# Sheet1.net
KiCad netlist of a schematic drawn in Altium Designer
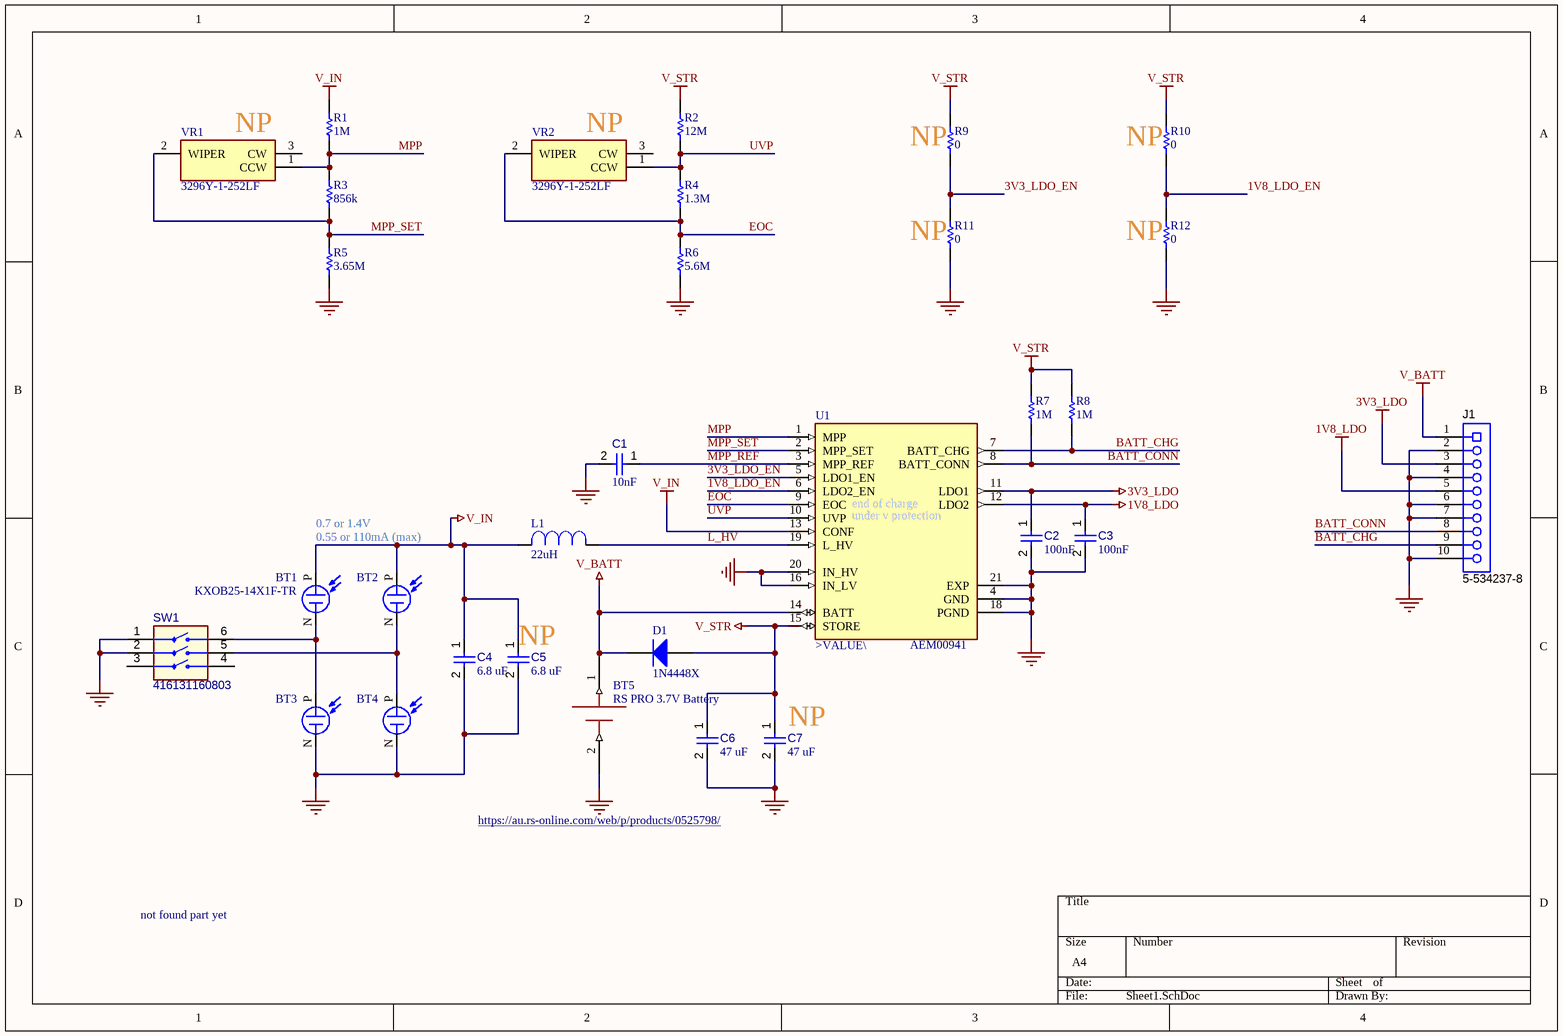
[diagram p0: Sheet1.SchDoc]

(export (version "E")
  (design (tool "Eeschema 10.0.6"))
  (components
    (comp (ref "BT1")
      (value "KXOB25-14X1F-TR")
      (footprint "SOLAR_KXOB25-14X1F-TR")
      (description "Monocrystalline Solar Cell 30.7 mW 690 mV")
      (fields (field (name "MF") "ANYSOLAR Ltd"))
      (libsource (lib "KXOB25-14X1F-TR") (part "KXOB25-14X1F-TR"))
    )
    (comp (ref "BT2")
      (value "KXOB25-14X1F-TR")
      (footprint "SOLAR_KXOB25-14X1F-TR")
      (description "Monocrystalline Solar Cell 30.7 mW 690 mV")
      (fields (field (name "MF") "ANYSOLAR Ltd"))
      (libsource (lib "KXOB25-14X1F-TR") (part "KXOB25-14X1F-TR"))
    )
    (comp (ref "BT3")
      (value "KXOB25-14X1F-TR")
      (footprint "SOLAR_KXOB25-14X1F-TR")
      (description "Monocrystalline Solar Cell 30.7 mW 690 mV")
      (fields (field (name "MF") "ANYSOLAR Ltd"))
      (libsource (lib "KXOB25-14X1F-TR") (part "KXOB25-14X1F-TR"))
    )
    (comp (ref "BT4")
      (value "KXOB25-14X1F-TR")
      (footprint "SOLAR_KXOB25-14X1F-TR")
      (description "Monocrystalline Solar Cell 30.7 mW 690 mV")
      (fields (field (name "MF") "ANYSOLAR Ltd"))
      (libsource (lib "KXOB25-14X1F-TR") (part "KXOB25-14X1F-TR"))
    )
    (comp (ref "BT5") (value "RS PRO 3.7V Battery") (libsource (lib "Schlib3") (part "RS PRO 3.7V Battery")))
    (comp (ref "C1")
      (value "10nF")
      (footprint "CAPC1608X94X35NL15T15")
      (description "Chip Capacitor, 1 uF, +/- 10%, 16 V, 0603 (1608 Metric)")
      (fields (field (name "TOLERANCE") "10%") (field (name "Comment") "Capacitor 1 uF +/- 10% 16 V 0603"))
      (libsource (lib "University of New South Wales") (part "CAP-NP-2"))
    )
    (comp (ref "C2")
      (value "100nF")
      (footprint "CAPC1608X94X35NL15T15")
      (description "Chip Capacitor, 1 uF, +/- 10%, 16 V, 0603 (1608 Metric)")
      (fields (field (name "TOLERANCE") "10%") (field (name "Comment") "Capacitor 1 uF +/- 10% 16 V 0603"))
      (libsource (lib "University of New South Wales") (part "CAP-NP-2"))
    )
    (comp (ref "C3")
      (value "100nF")
      (footprint "CAPC1608X94X35NL15T15")
      (description "Chip Capacitor, 1 uF, +/- 10%, 16 V, 0603 (1608 Metric)")
      (fields (field (name "TOLERANCE") "10%") (field (name "Comment") "Capacitor 1 uF +/- 10% 16 V 0603"))
      (libsource (lib "University of New South Wales") (part "CAP-NP-2"))
    )
    (comp (ref "C4")
      (value "6.8 uF")
      (footprint "CAPC0805(2012)145_L")
      (description "Chip Capacitor, 100µF +/-20%, 6.3V, 0805, Thickness 1.45 mm")
      (fields (field (name "TOLERANCE") "10%") (field (name "Comment") "Capacitor 100µF +/-20% 6.3V 0805"))
      (libsource (lib "University of New South Wales") (part "CAP-NP-2"))
    )
    (comp (ref "C5")
      (value "6.8 uF")
      (footprint "CAPC0805(2012)145_L")
      (description "Chip Capacitor, 100µF +/-20%, 6.3V, 0805, Thickness 1.45 mm")
      (fields (field (name "TOLERANCE") "10%") (field (name "Comment") "Capacitor 100µF +/-20% 6.3V 0805"))
      (libsource (lib "University of New South Wales") (part "CAP-NP-2"))
    )
    (comp (ref "C6")
      (value "47 uF")
      (footprint "CAPC0805(2012)145_L")
      (description "Chip Capacitor, 100µF +/-20%, 6.3V, 0805, Thickness 1.45 mm")
      (fields (field (name "TOLERANCE") "10%") (field (name "Comment") "Capacitor 100µF +/-20% 6.3V 0805"))
      (libsource (lib "University of New South Wales") (part "CAP-NP-2"))
    )
    (comp (ref "C7")
      (value "47 uF")
      (footprint "CAPC0805(2012)145_L")
      (description "Chip Capacitor, 100µF +/-20%, 6.3V, 0805, Thickness 1.45 mm")
      (fields (field (name "TOLERANCE") "10%") (field (name "Comment") "Capacitor 100µF +/-20% 6.3V 0805"))
      (libsource (lib "University of New South Wales") (part "CAP-NP-2"))
    )
    (comp (ref "D1")
      (value "1N4448X")
      (footprint "FAIR-SOD-323_V")
      (description "Small Signal Diode, 75 V, 0.15 A, -55 to 150 degC, 2-Pin SOD-323, RoHS, Tape and Reel")
      (fields (field (name "MANUFACTURER") "Fairchild"))
      (libsource (lib "University of New South Wales") (part "D-AK-2"))
    )
    (comp (ref "J1")
      (value "5-534237-8")
      (footprint "TECO-5-534237-8_V")
      (fields (field (name "MANUFACTURER") "TE Connectivity"))
      (libsource (lib "University of New South Wales") (part "CN-1P-F-R10"))
    )
    (comp (ref "L1")
      (value "22uH")
      (footprint "INDM125125X600N")
      (fields (field (name "MF") "Eaton") (field (name "MP") "DR125471R"))
      (libsource (lib "DR125-471-R") (part "DR125-471-R"))
    )
    (comp (ref "R1")
      (value "1M")
      (footprint "RESC1608X55X25ML10T15")
      (description "Chip Resistor, 0 Ohm, 0.1 W, -55 to 155 degC, 0603 (1608 Metric)")
      (fields (field (name "POWER") "100mW") (field (name "TOLERANCE") "5%"))
      (libsource (lib "University of New South Wales") (part "RES-2"))
    )
    (comp (ref "R2")
      (value "12M")
      (footprint "RESC1608X55X25ML10T15")
      (description "Chip Resistor, 0 Ohm, 0.1 W, -55 to 155 degC, 0603 (1608 Metric)")
      (fields (field (name "POWER") "100mW") (field (name "TOLERANCE") "5%"))
      (libsource (lib "University of New South Wales") (part "RES-2"))
    )
    (comp (ref "R3")
      (value "856k")
      (footprint "RESC1608X55X25ML10T15")
      (description "Chip Resistor, 0 Ohm, 0.1 W, -55 to 155 degC, 0603 (1608 Metric)")
      (fields (field (name "POWER") "100mW") (field (name "TOLERANCE") "5%"))
      (libsource (lib "University of New South Wales") (part "RES-2"))
    )
    (comp (ref "R4")
      (value "1.3M")
      (footprint "RESC1608X55X25ML10T15")
      (description "Chip Resistor, 0 Ohm, 0.1 W, -55 to 155 degC, 0603 (1608 Metric)")
      (fields (field (name "POWER") "100mW") (field (name "TOLERANCE") "5%"))
      (libsource (lib "University of New South Wales") (part "RES-2"))
    )
    (comp (ref "R5")
      (value "3.65M")
      (footprint "RESC1608X55X25ML10T15")
      (description "Chip Resistor, 0 Ohm, 0.1 W, -55 to 155 degC, 0603 (1608 Metric)")
      (fields (field (name "POWER") "100mW") (field (name "TOLERANCE") "5%"))
      (libsource (lib "University of New South Wales") (part "RES-2"))
    )
    (comp (ref "R6")
      (value "5.6M")
      (footprint "RESC1608X55X25ML10T15")
      (description "Chip Resistor, 0 Ohm, 0.1 W, -55 to 155 degC, 0603 (1608 Metric)")
      (fields (field (name "POWER") "100mW") (field (name "TOLERANCE") "5%"))
      (libsource (lib "University of New South Wales") (part "RES-2"))
    )
    (comp (ref "R7")
      (value "1M")
      (footprint "RESC1608X55X25ML10T15")
      (description "Chip Resistor, 0 Ohm, 0.1 W, -55 to 155 degC, 0603 (1608 Metric)")
      (fields (field (name "POWER") "100mW") (field (name "TOLERANCE") "5%"))
      (libsource (lib "University of New South Wales") (part "RES-2"))
    )
    (comp (ref "R8")
      (value "1M")
      (footprint "RESC1608X55X25ML10T15")
      (description "Chip Resistor, 0 Ohm, 0.1 W, -55 to 155 degC, 0603 (1608 Metric)")
      (fields (field (name "POWER") "100mW") (field (name "TOLERANCE") "5%"))
      (libsource (lib "University of New South Wales") (part "RES-2"))
    )
    (comp (ref "R9")
      (value "0")
      (footprint "RESC1005X40X25ML05T10")
      (description "Chip Resistor, 0 Ohm, 0.063 W, -55 to 155 degC, 0402 (1005 Metric)")
      (fields (field (name "POWER") "63mW") (field (name "Comment") "Resistor 0R 0402 63 mW"))
      (libsource (lib "University of New South Wales") (part "RES-2"))
    )
    (comp (ref "R10")
      (value "0")
      (footprint "RESC1005X40X25ML05T10")
      (description "Chip Resistor, 0 Ohm, 0.063 W, -55 to 155 degC, 0402 (1005 Metric)")
      (fields (field (name "POWER") "63mW") (field (name "Comment") "Resistor 0R 0402 63 mW"))
      (libsource (lib "University of New South Wales") (part "RES-2"))
    )
    (comp (ref "R11")
      (value "0")
      (footprint "RESC1005X40X25ML05T10")
      (description "Chip Resistor, 0 Ohm, 0.063 W, -55 to 155 degC, 0402 (1005 Metric)")
      (fields (field (name "POWER") "63mW") (field (name "Comment") "Resistor 0R 0402 63 mW"))
      (libsource (lib "University of New South Wales") (part "RES-2"))
    )
    (comp (ref "R12")
      (value "0")
      (footprint "RESC1005X40X25ML05T10")
      (description "Chip Resistor, 0 Ohm, 0.063 W, -55 to 155 degC, 0402 (1005 Metric)")
      (fields (field (name "POWER") "63mW") (field (name "Comment") "Resistor 0R 0402 63 mW"))
      (libsource (lib "University of New South Wales") (part "RES-2"))
    )
    (comp (ref "SW1")
      (value "416131160803")
      (footprint "416131160803")
      (description "WS-DISV 1.27 mm small compact SMD Dip Switch with top tape")
      (libsource (lib "University of New South Wales") (part "CMP-00567-2"))
    )
    (comp (ref "U1")
      (value "AEM00941")
      (footprint "QFN40P300X300X100-21N")
      (description "Charger IC Multi-Chemistry 20-VFQFPN (3x3)")
      (fields (field (name "MF") "STMicroelectronics") (field (name "MP") "SPV1050TTR"))
      (libsource (lib "SPV1050TTR") (part "SPV1050TTR"))
    )
    (comp (ref "VR1")
      (value "3296Y-1-252LF")
      (footprint "SamacSys:3296Y_1")
      (description "Variable Resistor")
      (fields (field (name "MOUSER PART NUMBER") "652-3296Y-1-252LF"))
      (libsource (lib "*") (part "3296Y-1-252LF"))
    )
    (comp (ref "VR2")
      (value "3296Y-1-252LF")
      (footprint "SamacSys:3296Y_1")
      (description "Variable Resistor")
      (fields (field (name "MOUSER PART NUMBER") "652-3296Y-1-252LF"))
      (libsource (lib "*") (part "3296Y-1-252LF"))
    )
  )
  (nets
    (net (code "1") (name "/1V8_LDO_EN") (class "Default")
      (node (ref "R10") (pin "1") (pinfunction "1_1") (pintype "passive"))
      (node (ref "R12") (pin "2") (pinfunction "2_2") (pintype "passive"))
      (node (ref "U1") (pin "6") (pinfunction "LDO2_EN_6") (pintype "input"))
    )
    (net (code "2") (name "/3V3_LDO_EN") (class "Default")
      (node (ref "R11") (pin "2") (pinfunction "2_2") (pintype "passive"))
      (node (ref "R9") (pin "1") (pinfunction "1_1") (pintype "passive"))
      (node (ref "U1") (pin "5") (pinfunction "LDO1_EN_5") (pintype "input"))
    )
    (net (code "3") (name "/BATT_CHG") (class "Default")
      (node (ref "J1") (pin "9") (pinfunction "9_9") (pintype "passive"))
      (node (ref "R8") (pin "1") (pinfunction "1_1") (pintype "passive"))
      (node (ref "U1") (pin "7") (pinfunction "BATT_CHG_7") (pintype "output"))
    )
    (net (code "4") (name "/BATT_CONN") (class "Default")
      (node (ref "J1") (pin "8") (pinfunction "8_8") (pintype "passive"))
      (node (ref "R7") (pin "1") (pinfunction "1_1") (pintype "passive"))
      (node (ref "U1") (pin "8") (pinfunction "BATT_CONN_8") (pintype "output"))
    )
    (net (code "5") (name "/EOC") (class "Default")
      (node (ref "R4") (pin "1") (pinfunction "1_1") (pintype "passive"))
      (node (ref "R6") (pin "2") (pinfunction "2_2") (pintype "passive"))
      (node (ref "U1") (pin "9") (pinfunction "EOC_9") (pintype "input"))
      (node (ref "VR2") (pin "2") (pinfunction "WIPER_2") (pintype "passive"))
    )
    (net (code "6") (name "/L_HV") (class "Default")
      (node (ref "L1") (pin "1") (pinfunction "1_1") (pintype "passive"))
      (node (ref "U1") (pin "19") (pinfunction "L_HV_19") (pintype "input"))
    )
    (net (code "7") (name "/MPP") (class "Default")
      (node (ref "R1") (pin "1") (pinfunction "1_1") (pintype "passive"))
      (node (ref "R3") (pin "2") (pinfunction "2_2") (pintype "passive"))
      (node (ref "U1") (pin "1") (pinfunction "MPP_1") (pintype "input"))
      (node (ref "VR1") (pin "1") (pinfunction "CCW_1") (pintype "passive"))
    )
    (net (code "8") (name "/MPP_REF") (class "Default")
      (node (ref "C1") (pin "1") (pinfunction "1_1") (pintype "passive"))
      (node (ref "U1") (pin "3") (pinfunction "MPP_REF_3") (pintype "input"))
    )
    (net (code "9") (name "/MPP_SET") (class "Default")
      (node (ref "R3") (pin "1") (pinfunction "1_1") (pintype "passive"))
      (node (ref "R5") (pin "2") (pinfunction "2_2") (pintype "passive"))
      (node (ref "U1") (pin "2") (pinfunction "MPP_SET_2") (pintype "input"))
      (node (ref "VR1") (pin "2") (pinfunction "WIPER_2") (pintype "passive"))
    )
    (net (code "10") (name "/UVP") (class "Default")
      (node (ref "R2") (pin "1") (pinfunction "1_1") (pintype "passive"))
      (node (ref "R4") (pin "2") (pinfunction "2_2") (pintype "passive"))
      (node (ref "U1") (pin "10") (pinfunction "UVP_10") (pintype "input"))
      (node (ref "VR2") (pin "1") (pinfunction "CCW_1") (pintype "passive"))
    )
    (net (code "11") (name "1V8_LDO") (class "Default")
      (node (ref "C3") (pin "1") (pinfunction "1_1") (pintype "passive"))
      (node (ref "J1") (pin "5") (pinfunction "5_5") (pintype "passive"))
      (node (ref "U1") (pin "12") (pinfunction "LDO2_12") (pintype "output"))
    )
    (net (code "12") (name "3V3_LDO") (class "Default")
      (node (ref "C2") (pin "1") (pinfunction "1_1") (pintype "passive"))
      (node (ref "J1") (pin "3") (pinfunction "3_3") (pintype "passive"))
      (node (ref "U1") (pin "11") (pinfunction "LDO1_11") (pintype "output"))
    )
    (net (code "13") (name "GND") (class "Default")
      (node (ref "BT3") (pin "N") (pinfunction "N_N") (pintype "passive"))
      (node (ref "BT4") (pin "N") (pinfunction "N_N") (pintype "passive"))
      (node (ref "BT5") (pin "2") (pinfunction "BATT_NEG_2") (pintype "input"))
      (node (ref "C1") (pin "2") (pinfunction "2_2") (pintype "passive"))
      (node (ref "C2") (pin "2") (pinfunction "2_2") (pintype "passive"))
      (node (ref "C3") (pin "2") (pinfunction "2_2") (pintype "passive"))
      (node (ref "C4") (pin "2") (pinfunction "2_2") (pintype "passive"))
      (node (ref "C5") (pin "2") (pinfunction "2_2") (pintype "passive"))
      (node (ref "C6") (pin "2") (pinfunction "2_2") (pintype "passive"))
      (node (ref "C7") (pin "2") (pinfunction "2_2") (pintype "passive"))
      (node (ref "J1") (pin "10") (pinfunction "10_10") (pintype "passive"))
      (node (ref "J1") (pin "2") (pinfunction "2_2") (pintype "passive"))
      (node (ref "J1") (pin "4") (pinfunction "4_4") (pintype "passive"))
      (node (ref "J1") (pin "6") (pinfunction "6_6") (pintype "passive"))
      (node (ref "J1") (pin "7") (pinfunction "7_7") (pintype "passive"))
      (node (ref "R11") (pin "1") (pinfunction "1_1") (pintype "passive"))
      (node (ref "R12") (pin "1") (pinfunction "1_1") (pintype "passive"))
      (node (ref "R5") (pin "1") (pinfunction "1_1") (pintype "passive"))
      (node (ref "R6") (pin "1") (pinfunction "1_1") (pintype "passive"))
      (node (ref "SW1") (pin "1") (pinfunction "1_1") (pintype "passive"))
      (node (ref "SW1") (pin "2") (pinfunction "2_2") (pintype "passive"))
      (node (ref "U1") (pin "16") (pinfunction "IN_LV_16") (pintype "input"))
      (node (ref "U1") (pin "18") (pinfunction "PGND_18") (pintype "power_in"))
      (node (ref "U1") (pin "20") (pinfunction "IN_HV_20") (pintype "input"))
      (node (ref "U1") (pin "21") (pinfunction "EXP_21") (pintype "power_in"))
      (node (ref "U1") (pin "4") (pinfunction "GND_4") (pintype "power_in"))
    )
    (net (code "14") (name "Net-(BT1-PadN)") (class "Default")
      (node (ref "BT1") (pin "N") (pinfunction "N_N") (pintype "passive"))
      (node (ref "BT3") (pin "P") (pinfunction "P_P") (pintype "passive"))
      (node (ref "SW1") (pin "6") (pinfunction "6_6") (pintype "passive"))
    )
    (net (code "15") (name "Net-(BT2-PadN)") (class "Default")
      (node (ref "BT2") (pin "N") (pinfunction "N_N") (pintype "passive"))
      (node (ref "BT4") (pin "P") (pinfunction "P_P") (pintype "passive"))
      (node (ref "SW1") (pin "5") (pinfunction "5_5") (pintype "passive"))
    )
    (net (code "16") (name "V_BATT") (class "Default")
      (node (ref "BT5") (pin "1") (pinfunction "BATT_POS_1") (pintype "output"))
      (node (ref "D1") (pin "2") (pinfunction "K_2") (pintype "passive"))
      (node (ref "J1") (pin "1") (pinfunction "1_1") (pintype "passive"))
      (node (ref "U1") (pin "14") (pinfunction "BATT_14") (pintype "bidirectional"))
    )
    (net (code "17") (name "V_IN") (class "Default")
      (node (ref "BT1") (pin "P") (pinfunction "P_P") (pintype "passive"))
      (node (ref "BT2") (pin "P") (pinfunction "P_P") (pintype "passive"))
      (node (ref "C4") (pin "1") (pinfunction "1_1") (pintype "passive"))
      (node (ref "C5") (pin "1") (pinfunction "1_1") (pintype "passive"))
      (node (ref "L1") (pin "2") (pinfunction "2_2") (pintype "passive"))
      (node (ref "R1") (pin "2") (pinfunction "2_2") (pintype "passive"))
      (node (ref "U1") (pin "13") (pinfunction "CONF_13") (pintype "input"))
    )
    (net (code "18") (name "V_STR") (class "Default")
      (node (ref "C6") (pin "1") (pinfunction "1_1") (pintype "passive"))
      (node (ref "C7") (pin "1") (pinfunction "1_1") (pintype "passive"))
      (node (ref "D1") (pin "1") (pinfunction "A_1") (pintype "passive"))
      (node (ref "R10") (pin "2") (pinfunction "2_2") (pintype "passive"))
      (node (ref "R2") (pin "2") (pinfunction "2_2") (pintype "passive"))
      (node (ref "R7") (pin "2") (pinfunction "2_2") (pintype "passive"))
      (node (ref "R8") (pin "2") (pinfunction "2_2") (pintype "passive"))
      (node (ref "R9") (pin "2") (pinfunction "2_2") (pintype "passive"))
      (node (ref "U1") (pin "15") (pinfunction "STORE_15") (pintype "bidirectional"))
    )
    (net (code "19") (name "unconnected-(SW1-Pad3)") (class "Default")
      (node (ref "SW1") (pin "3") (pinfunction "3_3") (pintype "passive"))
    )
    (net (code "20") (name "unconnected-(SW1-Pad4)") (class "Default")
      (node (ref "SW1") (pin "4") (pinfunction "4_4") (pintype "passive"))
    )
    (net (code "21") (name "unconnected-(VR1-CW-Pad3)") (class "Default")
      (node (ref "VR1") (pin "3") (pinfunction "CW_3") (pintype "passive"))
    )
    (net (code "22") (name "unconnected-(VR2-CW-Pad3)") (class "Default")
      (node (ref "VR2") (pin "3") (pinfunction "CW_3") (pintype "passive"))
    )
  )
)
